# 1_3_1_Power_board_BAT1_BAT2.net
KiCad netlist of a schematic drawn in Altium Designer
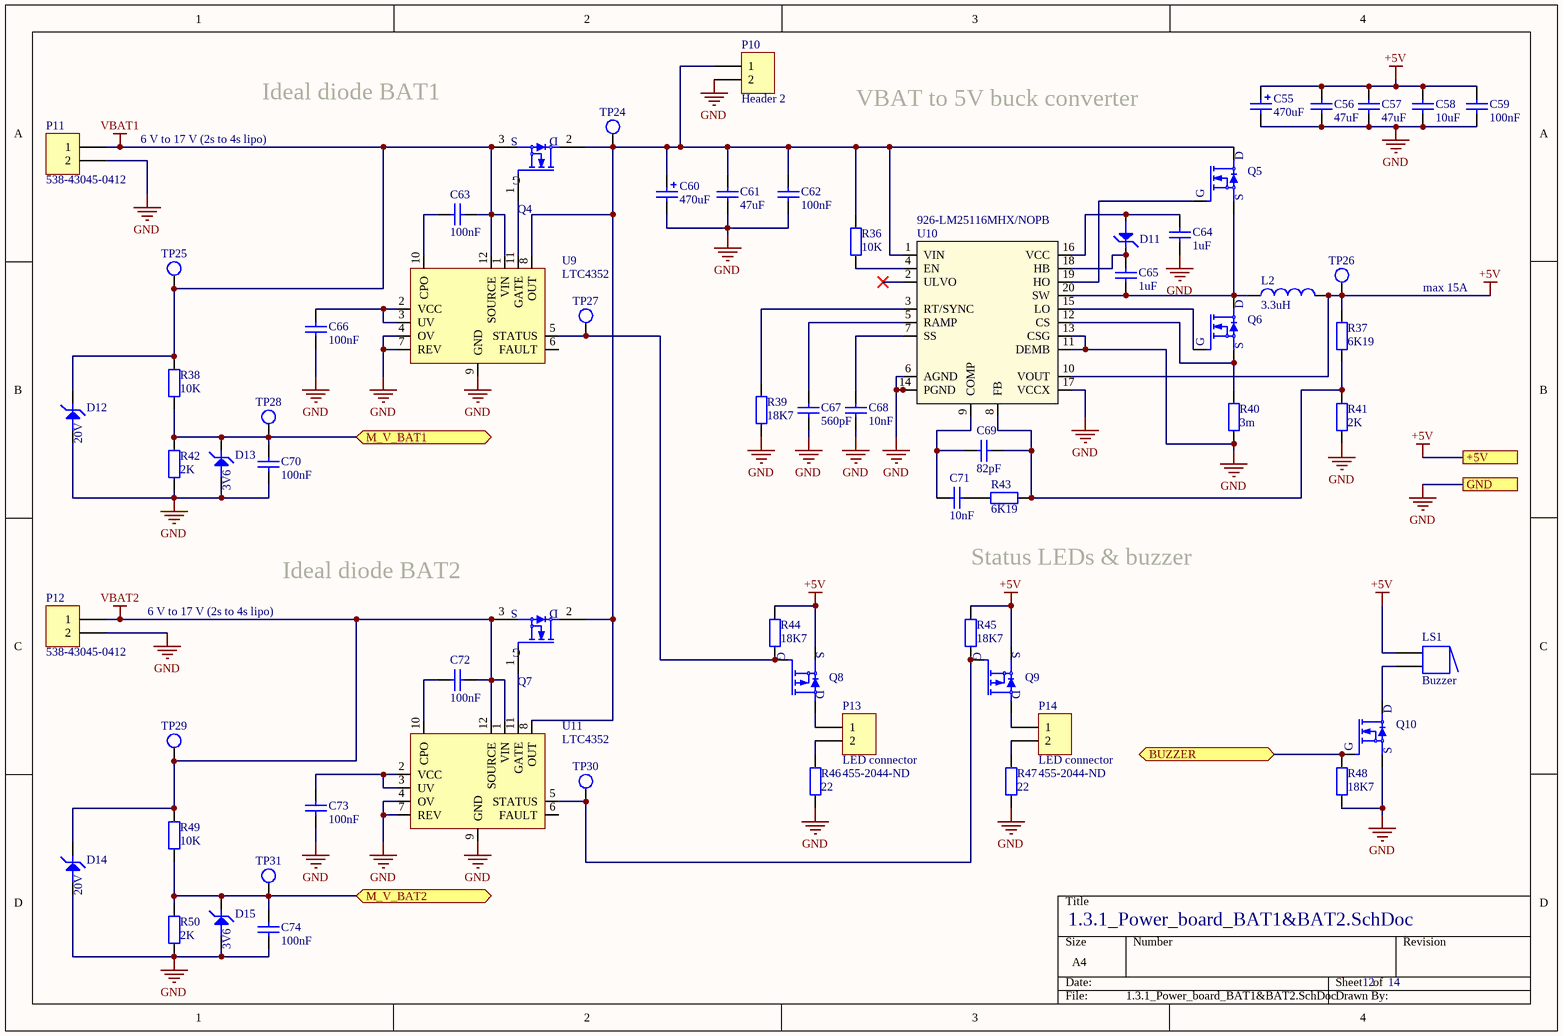
[diagram p0: 1.3.1_Power_board_BAT1&BAT2.SchDoc]

(export (version "E")
  (design (tool "Eeschema 10.0.6"))
  (components
    (comp (ref "C55")
      (value "470uF")
      (footprint "PCV_10x10")
      (description "Polarized Capacitor")
      (libsource (lib "Rocket_library") (part "C_pol_470uF_elec"))
    )
    (comp (ref "C56")
      (value "47uF")
      (footprint "CAP1206W")
      (description "Capacitor")
      (libsource (lib "Rocket_library") (part "C_47uF_25v_1206"))
    )
    (comp (ref "C57")
      (value "47uF")
      (footprint "CAP1206W")
      (description "Capacitor")
      (libsource (lib "Rocket_library") (part "C_47uF_25v_1206"))
    )
    (comp (ref "C58")
      (value "10uF")
      (footprint "CAP0805W")
      (description "Capacitor")
      (libsource (lib "Rocket_library") (part "C_10uF_16v"))
    )
    (comp (ref "C59")
      (value "100nF")
      (footprint "CAP0603R")
      (description "Capacitor")
      (libsource (lib "Rocket_library") (part "C_100nF"))
    )
    (comp (ref "C60")
      (value "470uF")
      (footprint "PCV_10x10")
      (description "Polarized Capacitor")
      (libsource (lib "Rocket_library") (part "C_pol_470uF_elec"))
    )
    (comp (ref "C61")
      (value "47uF")
      (footprint "CAP1206W")
      (description "Capacitor")
      (libsource (lib "Rocket_library") (part "C_47uF_25v_1206"))
    )
    (comp (ref "C62")
      (value "100nF")
      (footprint "CAP0603R")
      (description "Capacitor")
      (libsource (lib "Rocket_library") (part "C_100nF"))
    )
    (comp (ref "C63")
      (value "100nF")
      (footprint "CAP0603R")
      (description "Capacitor")
      (libsource (lib "Rocket_library") (part "C_100nF"))
    )
    (comp (ref "C64")
      (value "1uF")
      (footprint "CAP0603R")
      (description "Capacitor")
      (libsource (lib "Rocket_library") (part "C_1uF_50v"))
    )
    (comp (ref "C65")
      (value "1uF")
      (footprint "CAP0603R")
      (description "Capacitor")
      (libsource (lib "Rocket_library") (part "C_1uF_50v"))
    )
    (comp (ref "C66")
      (value "100nF")
      (footprint "CAP0603R")
      (description "Capacitor")
      (libsource (lib "Rocket_library") (part "C_100nF"))
    )
    (comp (ref "C67")
      (value "560pF")
      (footprint "CAP0603R")
      (description "Capacitor")
      (libsource (lib "Rocket_library") (part "C_560pF_50V"))
    )
    (comp (ref "C68")
      (value "10nF")
      (footprint "CAP0603R")
      (description "Capacitor")
      (libsource (lib "Rocket_library") (part "C_10nF"))
    )
    (comp (ref "C69")
      (value "82pF")
      (footprint "CAP0603R")
      (description "Capacitor")
      (libsource (lib "Rocket_library") (part "C_82pF_50V"))
    )
    (comp (ref "C70")
      (value "100nF")
      (footprint "CAP0603R")
      (description "Capacitor")
      (libsource (lib "Rocket_library") (part "C_100nF"))
    )
    (comp (ref "C71")
      (value "10nF")
      (footprint "CAP0603R")
      (description "Capacitor")
      (libsource (lib "Rocket_library") (part "C_10nF"))
    )
    (comp (ref "C72")
      (value "100nF")
      (footprint "CAP0603R")
      (description "Capacitor")
      (libsource (lib "Rocket_library") (part "C_100nF"))
    )
    (comp (ref "C73")
      (value "100nF")
      (footprint "CAP0603R")
      (description "Capacitor")
      (libsource (lib "Rocket_library") (part "C_100nF"))
    )
    (comp (ref "C74")
      (value "100nF")
      (footprint "CAP0603R")
      (description "Capacitor")
      (libsource (lib "Rocket_library") (part "C_100nF"))
    )
    (comp (ref "D11")
      (value "DS_NRVB0530T3G")
      (footprint "SOD123")
      (libsource (lib "Rocket_library") (part "DS_NRVB0530T3G"))
    )
    (comp (ref "D12")
      (value "20V")
      (footprint "DO-214AA")
      (description "Zener Diodes 5W 20V")
      (libsource (lib "Rocket_library") (part "DZ_20V"))
    )
    (comp (ref "D13")
      (value "3V6")
      (footprint "SOT23")
      (description "Zener Diodes 3.6V 225mW")
      (libsource (lib "Rocket_library") (part "DZ_3V6_MMBZ522"))
    )
    (comp (ref "D14")
      (value "20V")
      (footprint "DO-214AA")
      (description "Zener Diodes 5W 20V")
      (libsource (lib "Rocket_library") (part "DZ_20V"))
    )
    (comp (ref "D15")
      (value "3V6")
      (footprint "SOT23")
      (description "Zener Diodes 3.6V 225mW")
      (libsource (lib "Rocket_library") (part "DZ_3V6_MMBZ522"))
    )
    (comp (ref "L2")
      (value "3.3uH")
      (footprint "IHLP_Inductor")
      (description "Inductor")
      (libsource (lib "Rocket_library") (part "L_3.3uH"))
    )
    (comp (ref "LS1")
      (value "Buzzer")
      (footprint "CT-1205C-SMT")
      (description "Magnetic Transducer Buzzer 5VDC")
      (libsource (lib "Rocket_library") (part "Buzzer_CT-1205C-SMT-TR"))
    )
    (comp (ref "P10")
      (value "Header 2")
      (footprint "Con Prov 2P Power")
      (description "Juste pour tester!!!")
      (libsource (lib "Rocket_library") (part "Header 2"))
    )
    (comp (ref "P11")
      (value "Header MicroFit 2")
      (footprint "Con 2P Power and MicroFit 4P")
      (fields (field (name "SUPPLIER PART NUMBER 1") "538-43045-0412"))
      (libsource (lib "Rocket_library") (part "MicroFit and other Headers 2p"))
    )
    (comp (ref "P12")
      (value "Header MicroFit 2")
      (footprint "Con 2P Power and MicroFit 4P")
      (fields (field (name "SUPPLIER PART NUMBER 1") "538-43045-0412"))
      (libsource (lib "Rocket_library") (part "MicroFit and other Headers 2p"))
    )
    (comp (ref "P13")
      (value "LED connector")
      (footprint "CON_JST_XA_ S02B-XASS-1")
      (description "Header 2p JST XA 3A right angle")
      (fields (field (name "SUPPLIER PART NUMBER 1") "455-2044-ND"))
      (libsource (lib "Rocket_library") (part "Header 2p JST XA 3A right angle"))
    )
    (comp (ref "P14")
      (value "LED connector")
      (footprint "CON_JST_XA_ S02B-XASS-1")
      (description "Header 2p JST XA 3A right angle")
      (fields (field (name "SUPPLIER PART NUMBER 1") "455-2044-ND"))
      (libsource (lib "Rocket_library") (part "Header 2p JST XA 3A right angle"))
    )
    (comp (ref "Q4")
      (value "MOSFET_N")
      (footprint "TO220")
      (libsource (lib "Rocket_library") (part "MOSFET_IPP029N06NAKSA1"))
    )
    (comp (ref "Q5")
      (value "MOSFET_N")
      (footprint "TO252")
      (libsource (lib "Rocket_library") (part "MOSFET_DMTH4007LK3-13"))
    )
    (comp (ref "Q6")
      (value "MOSFET_N")
      (footprint "TO252")
      (libsource (lib "Rocket_library") (part "MOSFET_DMTH4007LK3-13"))
    )
    (comp (ref "Q7")
      (value "MOSFET_N")
      (footprint "TO220")
      (libsource (lib "Rocket_library") (part "MOSFET_IPP029N06NAKSA1"))
    )
    (comp (ref "Q8")
      (value "MOSFET_P")
      (footprint "SOT23")
      (description "MOSFET 40V P-channel Trench MOSFET SOT-23-3")
      (libsource (lib "Rocket_library") (part "MOSFET_P_ 20V_1.5A"))
    )
    (comp (ref "Q9")
      (value "MOSFET_P")
      (footprint "SOT23")
      (description "MOSFET 40V P-channel Trench MOSFET SOT-23-3")
      (libsource (lib "Rocket_library") (part "MOSFET_P_ 20V_1.5A"))
    )
    (comp (ref "Q10")
      (value "MOSFET_N")
      (footprint "SOT-323-3")
      (description "MOSFET N-Ch 20V 1.4A SOT-323-3")
      (libsource (lib "Rocket_library") (part "MOSFET_N_ 20V_1.4A"))
    )
    (comp (ref "R36")
      (value "10K")
      (footprint "0603")
      (description "0.1W 10K")
      (libsource (lib "Rocket_library") (part "R_0603_01W_10K"))
    )
    (comp (ref "R37")
      (value "6K19")
      (footprint "0603")
      (description "0.1W 6K19")
      (libsource (lib "Rocket_library") (part "R_0603_01W_6K2"))
    )
    (comp (ref "R38")
      (value "10K")
      (footprint "0603")
      (description "0.1W 10K")
      (libsource (lib "Rocket_library") (part "R_0603_01W_10K"))
    )
    (comp (ref "R39")
      (value "18K7")
      (footprint "0603")
      (description "0.1W 18K7")
      (libsource (lib "Rocket_library") (part "R_0603_01W_18K7"))
    )
    (comp (ref "R40")
      (value "3m")
      (footprint "2010")
      (description "2W 3mOhm")
      (libsource (lib "Rocket_library") (part "R_2010_2W_3mOhm"))
    )
    (comp (ref "R41")
      (value "2K")
      (footprint "0603")
      (description "0.1W 2K")
      (libsource (lib "Rocket_library") (part "R_0603_01W_2K"))
    )
    (comp (ref "R42")
      (value "2K")
      (footprint "0603")
      (description "0.1W 2K")
      (libsource (lib "Rocket_library") (part "R_0603_01W_2K"))
    )
    (comp (ref "R43")
      (value "6K19")
      (footprint "0603")
      (description "0.1W 6K19")
      (libsource (lib "") (part "R_0603_01W_6K2_1"))
    )
    (comp (ref "R44")
      (value "18K7")
      (footprint "0603")
      (description "0.1W 18K7")
      (libsource (lib "Rocket_library") (part "R_0603_01W_18K7"))
    )
    (comp (ref "R45")
      (value "18K7")
      (footprint "0603")
      (description "0.1W 18K7")
      (libsource (lib "Rocket_library") (part "R_0603_01W_18K7"))
    )
    (comp (ref "R46")
      (value "22")
      (footprint "0603")
      (description "0.25W 22Ohm")
      (libsource (lib "Rocket_library") (part "R_0603_025W_22Ohm"))
    )
    (comp (ref "R47")
      (value "22")
      (footprint "0603")
      (description "0.25W 22Ohm")
      (libsource (lib "Rocket_library") (part "R_0603_025W_22Ohm"))
    )
    (comp (ref "R48")
      (value "18K7")
      (footprint "0603")
      (description "0.1W 18K7")
      (libsource (lib "Rocket_library") (part "R_0603_01W_18K7"))
    )
    (comp (ref "R49")
      (value "10K")
      (footprint "0603")
      (description "0.1W 10K")
      (libsource (lib "Rocket_library") (part "R_0603_01W_10K"))
    )
    (comp (ref "R50")
      (value "2K")
      (footprint "0603")
      (description "0.1W 2K")
      (libsource (lib "Rocket_library") (part "R_0603_01W_2K"))
    )
    (comp (ref "TP24")
      (value "Test point")
      (footprint "TP")
      (libsource (lib "Rocket_library") (part "Test point"))
    )
    (comp (ref "TP25")
      (value "Test point")
      (footprint "TP")
      (libsource (lib "Rocket_library") (part "Test point"))
    )
    (comp (ref "TP26")
      (value "Test point")
      (footprint "TP")
      (libsource (lib "Rocket_library") (part "Test point"))
    )
    (comp (ref "TP27")
      (value "Test point")
      (footprint "TP")
      (libsource (lib "Rocket_library") (part "Test point"))
    )
    (comp (ref "TP28")
      (value "Test point")
      (footprint "TP")
      (libsource (lib "Rocket_library") (part "Test point"))
    )
    (comp (ref "TP29")
      (value "Test point")
      (footprint "TP")
      (libsource (lib "Rocket_library") (part "Test point"))
    )
    (comp (ref "TP30")
      (value "Test point")
      (footprint "TP")
      (libsource (lib "Rocket_library") (part "Test point"))
    )
    (comp (ref "TP31")
      (value "Test point")
      (footprint "TP")
      (libsource (lib "Rocket_library") (part "Test point"))
    )
    (comp (ref "U9")
      (value "LTC4352")
      (footprint "TSOP612")
      (libsource (lib "Rocket_library") (part "LTC4352"))
    )
    (comp (ref "U10")
      (value "LM25116MHX/NOPB")
      (footprint "HTSSOP 20")
      (description "WIDE RANGE SYNC BUCK")
      (fields (field (name "SUPPLIER PART NUMBER 1") "926-LM25116MHX/NOPB"))
      (libsource (lib "Rocket_library") (part "LM25116MHX/NOPB"))
    )
    (comp (ref "U11")
      (value "LTC4352")
      (footprint "TSOP612")
      (libsource (lib "Rocket_library") (part "LTC4352"))
    )
  )
  (nets
    (net (code "1") (name "+5V") (class "Default")
      (node (ref "C55") (pin "1") (pinfunction "1_1") (pintype "passive"))
      (node (ref "C56") (pin "2") (pinfunction "2_2") (pintype "passive"))
      (node (ref "C57") (pin "2") (pinfunction "2_2") (pintype "passive"))
      (node (ref "C58") (pin "2") (pinfunction "2_2") (pintype "passive"))
      (node (ref "C59") (pin "2") (pinfunction "2_2") (pintype "passive"))
      (node (ref "L2") (pin "2") (pinfunction "2_2") (pintype "passive"))
      (node (ref "LS1") (pin "1") (pinfunction "1_1") (pintype "passive"))
      (node (ref "Q8") (pin "2") (pinfunction "S_2") (pintype "passive"))
      (node (ref "Q9") (pin "2") (pinfunction "S_2") (pintype "passive"))
      (node (ref "R37") (pin "2") (pinfunction "2_2") (pintype "passive"))
      (node (ref "R44") (pin "2") (pinfunction "2_2") (pintype "passive"))
      (node (ref "R45") (pin "2") (pinfunction "2_2") (pintype "passive"))
      (node (ref "TP26") (pin "1") (pinfunction "1_1") (pintype "passive"))
      (node (ref "U10") (pin "10") (pinfunction "VOUT_10") (pintype "passive"))
    )
    (net (code "2") (name "/BUZZER") (class "Default")
      (node (ref "Q10") (pin "1") (pinfunction "G_1") (pintype "passive"))
      (node (ref "R48") (pin "2") (pinfunction "2_2") (pintype "passive"))
    )
    (net (code "3") (name "/M_V_BAT1") (class "Default")
      (node (ref "C70") (pin "2") (pinfunction "2_2") (pintype "passive"))
      (node (ref "D13") (pin "3") (pintype "passive"))
      (node (ref "R38") (pin "1") (pinfunction "1_1") (pintype "passive"))
      (node (ref "R42") (pin "2") (pinfunction "2_2") (pintype "passive"))
      (node (ref "TP28") (pin "1") (pinfunction "1_1") (pintype "passive"))
    )
    (net (code "4") (name "/M_V_BAT2") (class "Default")
      (node (ref "C74") (pin "2") (pinfunction "2_2") (pintype "passive"))
      (node (ref "D15") (pin "3") (pintype "passive"))
      (node (ref "R49") (pin "1") (pinfunction "1_1") (pintype "passive"))
      (node (ref "R50") (pin "2") (pinfunction "2_2") (pintype "passive"))
      (node (ref "TP31") (pin "1") (pinfunction "1_1") (pintype "passive"))
    )
    (net (code "5") (name "GND") (class "Default")
      (node (ref "C55") (pin "2") (pinfunction "2_2") (pintype "passive"))
      (node (ref "C56") (pin "1") (pinfunction "1_1") (pintype "passive"))
      (node (ref "C57") (pin "1") (pinfunction "1_1") (pintype "passive"))
      (node (ref "C58") (pin "1") (pinfunction "1_1") (pintype "passive"))
      (node (ref "C59") (pin "1") (pinfunction "1_1") (pintype "passive"))
      (node (ref "C60") (pin "2") (pinfunction "2_2") (pintype "passive"))
      (node (ref "C61") (pin "1") (pinfunction "1_1") (pintype "passive"))
      (node (ref "C62") (pin "1") (pinfunction "1_1") (pintype "passive"))
      (node (ref "C64") (pin "1") (pinfunction "1_1") (pintype "passive"))
      (node (ref "C66") (pin "1") (pinfunction "1_1") (pintype "passive"))
      (node (ref "C67") (pin "1") (pinfunction "1_1") (pintype "passive"))
      (node (ref "C68") (pin "1") (pinfunction "1_1") (pintype "passive"))
      (node (ref "C70") (pin "1") (pinfunction "1_1") (pintype "passive"))
      (node (ref "C73") (pin "1") (pinfunction "1_1") (pintype "passive"))
      (node (ref "C74") (pin "1") (pinfunction "1_1") (pintype "passive"))
      (node (ref "D12") (pin "A") (pintype "passive"))
      (node (ref "D13") (pin "1") (pintype "passive"))
      (node (ref "D14") (pin "A") (pintype "passive"))
      (node (ref "D15") (pin "1") (pintype "passive"))
      (node (ref "P10") (pin "2") (pinfunction "2_2") (pintype "passive"))
      (node (ref "P11") (pin "2") (pinfunction "2_2") (pintype "passive"))
      (node (ref "P12") (pin "2") (pinfunction "2_2") (pintype "passive"))
      (node (ref "Q10") (pin "2") (pinfunction "S_2") (pintype "passive"))
      (node (ref "R39") (pin "1") (pinfunction "1_1") (pintype "passive"))
      (node (ref "R40") (pin "1") (pinfunction "1_1") (pintype "passive"))
      (node (ref "R41") (pin "1") (pinfunction "1_1") (pintype "passive"))
      (node (ref "R42") (pin "1") (pinfunction "1_1") (pintype "passive"))
      (node (ref "R46") (pin "1") (pinfunction "1_1") (pintype "passive"))
      (node (ref "R47") (pin "1") (pinfunction "1_1") (pintype "passive"))
      (node (ref "R48") (pin "1") (pinfunction "1_1") (pintype "passive"))
      (node (ref "R50") (pin "1") (pinfunction "1_1") (pintype "passive"))
      (node (ref "U10") (pin "11") (pinfunction "DEMB_11") (pintype "passive"))
      (node (ref "U10") (pin "13") (pinfunction "CSG_13") (pintype "passive"))
      (node (ref "U10") (pin "14") (pinfunction "PGND_14") (pintype "passive"))
      (node (ref "U10") (pin "17") (pinfunction "VCCX_17") (pintype "passive"))
      (node (ref "U10") (pin "21") (pinfunction "EP_21") (pintype "passive"))
      (node (ref "U10") (pin "6") (pinfunction "AGND_6") (pintype "passive"))
      (node (ref "U11") (pin "4") (pinfunction "OV_4") (pintype "passive"))
      (node (ref "U11") (pin "7") (pinfunction "REV_7") (pintype "passive"))
      (node (ref "U11") (pin "9") (pinfunction "GND_9") (pintype "passive"))
      (node (ref "U9") (pin "4") (pinfunction "OV_4") (pintype "passive"))
      (node (ref "U9") (pin "7") (pinfunction "REV_7") (pintype "passive"))
      (node (ref "U9") (pin "9") (pinfunction "GND_9") (pintype "passive"))
    )
    (net (code "6") (name "Net-(C71-Pad1)") (class "Default")
      (node (ref "C71") (pin "1") (pinfunction "1_1") (pintype "passive"))
      (node (ref "R43") (pin "1") (pinfunction "1_1") (pintype "passive"))
    )
    (net (code "7") (name "Net-(P13-Pad2)") (class "Default")
      (node (ref "P13") (pin "2") (pinfunction "2_2") (pintype "passive"))
      (node (ref "R46") (pin "2") (pinfunction "2_2") (pintype "passive"))
    )
    (net (code "8") (name "Net-(P14-Pad2)") (class "Default")
      (node (ref "P14") (pin "2") (pinfunction "2_2") (pintype "passive"))
      (node (ref "R47") (pin "2") (pinfunction "2_2") (pintype "passive"))
    )
    (net (code "9") (name "Net-(Q4-D)") (class "Default")
      (node (ref "C60") (pin "1") (pinfunction "1_1") (pintype "passive"))
      (node (ref "C61") (pin "2") (pinfunction "2_2") (pintype "passive"))
      (node (ref "C62") (pin "2") (pinfunction "2_2") (pintype "passive"))
      (node (ref "P10") (pin "1") (pinfunction "1_1") (pintype "passive"))
      (node (ref "Q4") (pin "2") (pinfunction "D_2") (pintype "passive"))
      (node (ref "Q5") (pin "D") (pinfunction "D_D") (pintype "passive"))
      (node (ref "Q7") (pin "2") (pinfunction "D_2") (pintype "passive"))
      (node (ref "R36") (pin "2") (pinfunction "2_2") (pintype "passive"))
      (node (ref "TP24") (pin "1") (pinfunction "1_1") (pintype "passive"))
      (node (ref "U10") (pin "1") (pinfunction "VIN_1") (pintype "passive"))
      (node (ref "U11") (pin "8") (pinfunction "OUT_8") (pintype "passive"))
      (node (ref "U9") (pin "8") (pinfunction "OUT_8") (pintype "passive"))
    )
    (net (code "10") (name "Net-(Q4-G)") (class "Default")
      (node (ref "Q4") (pin "1") (pinfunction "G_1") (pintype "passive"))
      (node (ref "U9") (pin "11") (pinfunction "GATE_11") (pintype "passive"))
    )
    (net (code "11") (name "Net-(Q7-G)") (class "Default")
      (node (ref "Q7") (pin "1") (pinfunction "G_1") (pintype "passive"))
      (node (ref "U11") (pin "11") (pinfunction "GATE_11") (pintype "passive"))
    )
    (net (code "12") (name "Net-(Q8-D)") (class "Default")
      (node (ref "P13") (pin "1") (pinfunction "1_1") (pintype "passive"))
      (node (ref "Q8") (pin "3") (pinfunction "D_3") (pintype "passive"))
    )
    (net (code "13") (name "Net-(Q8-G)") (class "Default")
      (node (ref "Q8") (pin "1") (pinfunction "G_1") (pintype "passive"))
      (node (ref "R44") (pin "1") (pinfunction "1_1") (pintype "passive"))
      (node (ref "TP27") (pin "1") (pinfunction "1_1") (pintype "passive"))
      (node (ref "U9") (pin "5") (pinfunction "STATUS_5") (pintype "passive"))
    )
    (net (code "14") (name "Net-(Q9-D)") (class "Default")
      (node (ref "P14") (pin "1") (pinfunction "1_1") (pintype "passive"))
      (node (ref "Q9") (pin "3") (pinfunction "D_3") (pintype "passive"))
    )
    (net (code "15") (name "Net-(Q9-G)") (class "Default")
      (node (ref "Q9") (pin "1") (pinfunction "G_1") (pintype "passive"))
      (node (ref "R45") (pin "1") (pinfunction "1_1") (pintype "passive"))
      (node (ref "TP30") (pin "1") (pinfunction "1_1") (pintype "passive"))
      (node (ref "U11") (pin "5") (pinfunction "STATUS_5") (pintype "passive"))
    )
    (net (code "16") (name "Net-(Q10-D)") (class "Default")
      (node (ref "LS1") (pin "2") (pinfunction "2_2") (pintype "passive"))
      (node (ref "Q10") (pin "3") (pinfunction "D_3") (pintype "passive"))
    )
    (net (code "17") (name "Net-(U9-CPO)") (class "Default")
      (node (ref "C63") (pin "2") (pinfunction "2_2") (pintype "passive"))
      (node (ref "U9") (pin "10") (pinfunction "CPO_10") (pintype "passive"))
    )
    (net (code "18") (name "Net-(U9-UV)") (class "Default")
      (node (ref "C66") (pin "2") (pinfunction "2_2") (pintype "passive"))
      (node (ref "U9") (pin "2") (pinfunction "VCC_2") (pintype "passive"))
      (node (ref "U9") (pin "3") (pinfunction "UV_3") (pintype "passive"))
    )
    (net (code "19") (name "Net-(U10-COMP)") (class "Default")
      (node (ref "C69") (pin "2") (pinfunction "2_2") (pintype "passive"))
      (node (ref "C71") (pin "2") (pinfunction "2_2") (pintype "passive"))
      (node (ref "U10") (pin "9") (pinfunction "COMP_9") (pintype "passive"))
    )
    (net (code "20") (name "Net-(U10-CS)") (class "Default")
      (node (ref "Q6") (pin "S") (pinfunction "S_S") (pintype "passive"))
      (node (ref "R40") (pin "2") (pinfunction "2_2") (pintype "passive"))
      (node (ref "U10") (pin "12") (pinfunction "CS_12") (pintype "passive"))
    )
    (net (code "21") (name "Net-(U10-EN)") (class "Default")
      (node (ref "R36") (pin "1") (pinfunction "1_1") (pintype "passive"))
      (node (ref "U10") (pin "4") (pinfunction "EN_4") (pintype "passive"))
    )
    (net (code "22") (name "Net-(U10-FB)") (class "Default")
      (node (ref "C69") (pin "1") (pinfunction "1_1") (pintype "passive"))
      (node (ref "R37") (pin "1") (pinfunction "1_1") (pintype "passive"))
      (node (ref "R41") (pin "2") (pinfunction "2_2") (pintype "passive"))
      (node (ref "R43") (pin "2") (pinfunction "2_2") (pintype "passive"))
      (node (ref "U10") (pin "8") (pinfunction "FB_8") (pintype "passive"))
    )
    (net (code "23") (name "Net-(U10-HB)") (class "Default")
      (node (ref "C65") (pin "2") (pinfunction "2_2") (pintype "passive"))
      (node (ref "D11") (pin "1") (pintype "passive"))
      (node (ref "U10") (pin "18") (pinfunction "HB_18") (pintype "passive"))
    )
    (net (code "24") (name "Net-(U10-HO)") (class "Default")
      (node (ref "Q5") (pin "G") (pinfunction "G_G") (pintype "passive"))
      (node (ref "U10") (pin "19") (pinfunction "HO_19") (pintype "passive"))
    )
    (net (code "25") (name "Net-(U10-LO)") (class "Default")
      (node (ref "Q6") (pin "G") (pinfunction "G_G") (pintype "passive"))
      (node (ref "U10") (pin "15") (pinfunction "LO_15") (pintype "passive"))
    )
    (net (code "26") (name "Net-(U10-RAMP)") (class "Default")
      (node (ref "C67") (pin "2") (pinfunction "2_2") (pintype "passive"))
      (node (ref "U10") (pin "5") (pinfunction "RAMP_5") (pintype "passive"))
    )
    (net (code "27") (name "Net-(U10-RT{slash}SYNC)") (class "Default")
      (node (ref "R39") (pin "2") (pinfunction "2_2") (pintype "passive"))
      (node (ref "U10") (pin "3") (pinfunction "RT/SYNC_3") (pintype "passive"))
    )
    (net (code "28") (name "Net-(U10-SS)") (class "Default")
      (node (ref "C68") (pin "2") (pinfunction "2_2") (pintype "passive"))
      (node (ref "U10") (pin "7") (pinfunction "SS_7") (pintype "passive"))
    )
    (net (code "29") (name "Net-(U10-SW)") (class "Default")
      (node (ref "C65") (pin "1") (pinfunction "1_1") (pintype "passive"))
      (node (ref "L2") (pin "1") (pinfunction "1_1") (pintype "passive"))
      (node (ref "Q5") (pin "S") (pinfunction "S_S") (pintype "passive"))
      (node (ref "Q6") (pin "D") (pinfunction "D_D") (pintype "passive"))
      (node (ref "U10") (pin "20") (pinfunction "SW_20") (pintype "passive"))
    )
    (net (code "30") (name "Net-(U10-VCC)") (class "Default")
      (node (ref "C64") (pin "2") (pinfunction "2_2") (pintype "passive"))
      (node (ref "D11") (pin "2") (pintype "passive"))
      (node (ref "U10") (pin "16") (pinfunction "VCC_16") (pintype "passive"))
    )
    (net (code "31") (name "Net-(U11-CPO)") (class "Default")
      (node (ref "C72") (pin "2") (pinfunction "2_2") (pintype "passive"))
      (node (ref "U11") (pin "10") (pinfunction "CPO_10") (pintype "passive"))
    )
    (net (code "32") (name "Net-(U11-UV)") (class "Default")
      (node (ref "C73") (pin "2") (pinfunction "2_2") (pintype "passive"))
      (node (ref "U11") (pin "2") (pinfunction "VCC_2") (pintype "passive"))
      (node (ref "U11") (pin "3") (pinfunction "UV_3") (pintype "passive"))
    )
    (net (code "33") (name "VBAT1") (class "Default")
      (node (ref "C63") (pin "1") (pinfunction "1_1") (pintype "passive"))
      (node (ref "D12") (pin "C") (pintype "passive"))
      (node (ref "P11") (pin "1") (pinfunction "1_1") (pintype "passive"))
      (node (ref "Q4") (pin "3") (pinfunction "S_3") (pintype "passive"))
      (node (ref "R38") (pin "2") (pinfunction "2_2") (pintype "passive"))
      (node (ref "TP25") (pin "1") (pinfunction "1_1") (pintype "passive"))
      (node (ref "U9") (pin "1") (pinfunction "VIN_1") (pintype "passive"))
      (node (ref "U9") (pin "12") (pinfunction "SOURCE_12") (pintype "passive"))
    )
    (net (code "34") (name "VBAT2") (class "Default")
      (node (ref "C72") (pin "1") (pinfunction "1_1") (pintype "passive"))
      (node (ref "D14") (pin "C") (pintype "passive"))
      (node (ref "P12") (pin "1") (pinfunction "1_1") (pintype "passive"))
      (node (ref "Q7") (pin "3") (pinfunction "S_3") (pintype "passive"))
      (node (ref "R49") (pin "2") (pinfunction "2_2") (pintype "passive"))
      (node (ref "TP29") (pin "1") (pinfunction "1_1") (pintype "passive"))
      (node (ref "U11") (pin "1") (pinfunction "VIN_1") (pintype "passive"))
      (node (ref "U11") (pin "12") (pinfunction "SOURCE_12") (pintype "passive"))
    )
    (net (code "35") (name "unconnected-(U9-FAULT-Pad6)") (class "Default")
      (node (ref "U9") (pin "6") (pinfunction "FAULT_6") (pintype "passive"))
    )
    (net (code "36") (name "unconnected-(U10-ULVO-Pad2)") (class "Default")
      (node (ref "U10") (pin "2") (pinfunction "ULVO_2") (pintype "passive+no_connect"))
    )
    (net (code "37") (name "unconnected-(U11-FAULT-Pad6)") (class "Default")
      (node (ref "U11") (pin "6") (pinfunction "FAULT_6") (pintype "passive"))
    )
  )
)
